# Nintendo_DSi_USB-C.net
KiCad netlist of a schematic drawn in EAGLE
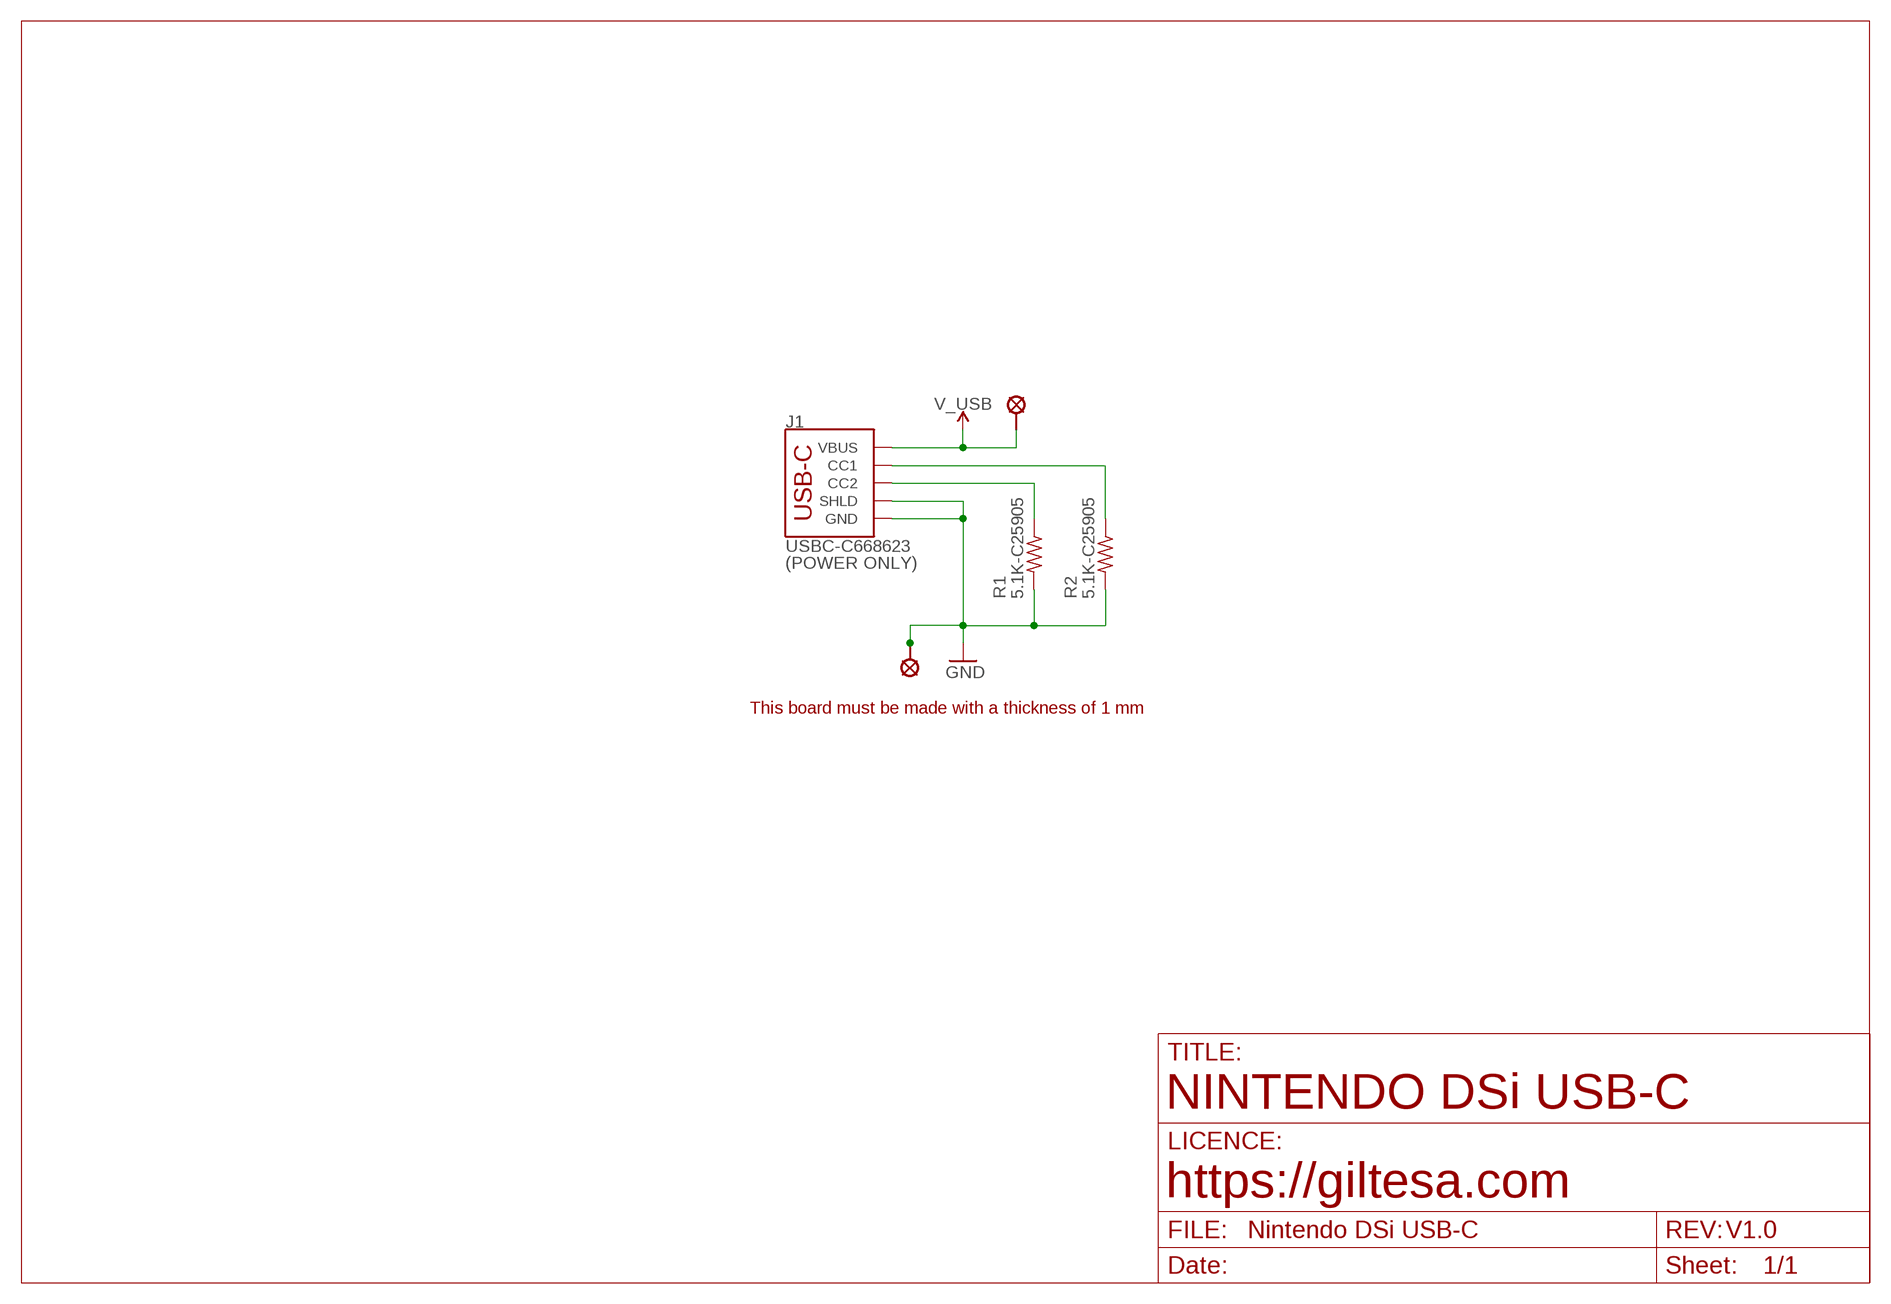
[diagram p0: schematic, sheet 1]

(export (version "E")
  (design (tool "Eeschema 10.0.6"))
  (components
    (comp (ref "J1")
      (value "USBC-C668623")
      (footprint "eagle-import:USB-C_6P")
      (libsource (lib "eagle-import") (part "USB-CPOWER"))
    )
    (comp (ref "R1")
      (value "5.1K-C25905")
      (footprint "eagle-import:R0402")
      (libsource (lib "eagle-import") (part "R0402"))
    )
    (comp (ref "R2")
      (value "5.1K-C25905")
      (footprint "eagle-import:R0402")
      (libsource (lib "eagle-import") (part "R0402"))
    )
    (comp (ref "U$2")
      (value "PAD_1.0H")
      (footprint "eagle-import:PAD_1.0_HALF_MASK")
      (libsource (lib "eagle-import") (part "PAD_1.0H"))
    )
    (comp (ref "U$3")
      (value "PAD_1.0H")
      (footprint "eagle-import:PAD_1.0_HALF_MASK")
      (libsource (lib "eagle-import") (part "PAD_1.0H"))
    )
    (comp (ref "U$4")
      (value "PAD_1.0H")
      (footprint "eagle-import:PAD_1.0_HALF_MASK")
      (libsource (lib "eagle-import") (part "PAD_1.0H"))
    )
    (comp (ref "U$5")
      (value "PAD_1.0H")
      (footprint "eagle-import:PAD_1.0_HALF_MASK")
      (libsource (lib "eagle-import") (part "PAD_1.0H"))
    )
  )
  (nets
    (net (code "1") (name "GND") (class "Default")
      (node (ref "J1") (pin "GND1") (pinfunction "GND_GND1") (pintype "bidirectional"))
      (node (ref "J1") (pin "GND2") (pinfunction "GND_GND2") (pintype "bidirectional"))
      (node (ref "J1") (pin "SHLD1") (pinfunction "SHLD_SHLD1") (pintype "bidirectional"))
      (node (ref "J1") (pin "SHLD2") (pinfunction "SHLD_SHLD2") (pintype "bidirectional"))
      (node (ref "J1") (pin "SHLD3") (pinfunction "SHLD_SHLD3") (pintype "bidirectional"))
      (node (ref "J1") (pin "SHLD4") (pinfunction "SHLD_SHLD4") (pintype "bidirectional"))
      (node (ref "J1") (pin "SHLD5") (pinfunction "SHLD_SHLD5") (pintype "bidirectional"))
      (node (ref "J1") (pin "SHLD6") (pinfunction "SHLD_SHLD6") (pintype "bidirectional"))
      (node (ref "J1") (pin "SHLD7") (pinfunction "SHLD_SHLD7") (pintype "bidirectional"))
      (node (ref "J1") (pin "SHLD8") (pinfunction "SHLD_SHLD8") (pintype "bidirectional"))
      (node (ref "R1") (pin "2") (pinfunction "2_2") (pintype "passive"))
      (node (ref "R2") (pin "2") (pinfunction "2_2") (pintype "passive"))
      (node (ref "U$3") (pin "P$1") (pinfunction "P$1_P$1") (pintype "bidirectional"))
      (node (ref "U$4") (pin "P$1") (pinfunction "P$1_P$1") (pintype "bidirectional"))
      (node (ref "U$5") (pin "P$1") (pinfunction "P$1_P$1") (pintype "bidirectional"))
    )
    (net (code "2") (name "Net-(J1-CC1)") (class "Default")
      (node (ref "J1") (pin "A5") (pinfunction "CC1_A5") (pintype "bidirectional"))
      (node (ref "R2") (pin "1") (pinfunction "1_1") (pintype "passive"))
    )
    (net (code "3") (name "Net-(J1-CC2)") (class "Default")
      (node (ref "J1") (pin "B5") (pinfunction "CC2_B5") (pintype "bidirectional"))
      (node (ref "R1") (pin "1") (pinfunction "1_1") (pintype "passive"))
    )
    (net (code "4") (name "V_USB") (class "Default")
      (node (ref "J1") (pin "VBUS1") (pinfunction "VBUS_VBUS1") (pintype "bidirectional"))
      (node (ref "J1") (pin "VBUS2") (pinfunction "VBUS_VBUS2") (pintype "bidirectional"))
      (node (ref "U$2") (pin "P$1") (pinfunction "P$1_P$1") (pintype "bidirectional"))
    )
  )
)
